# vca_B.net
KiCad netlist of a schematic drawn in Altium Designer
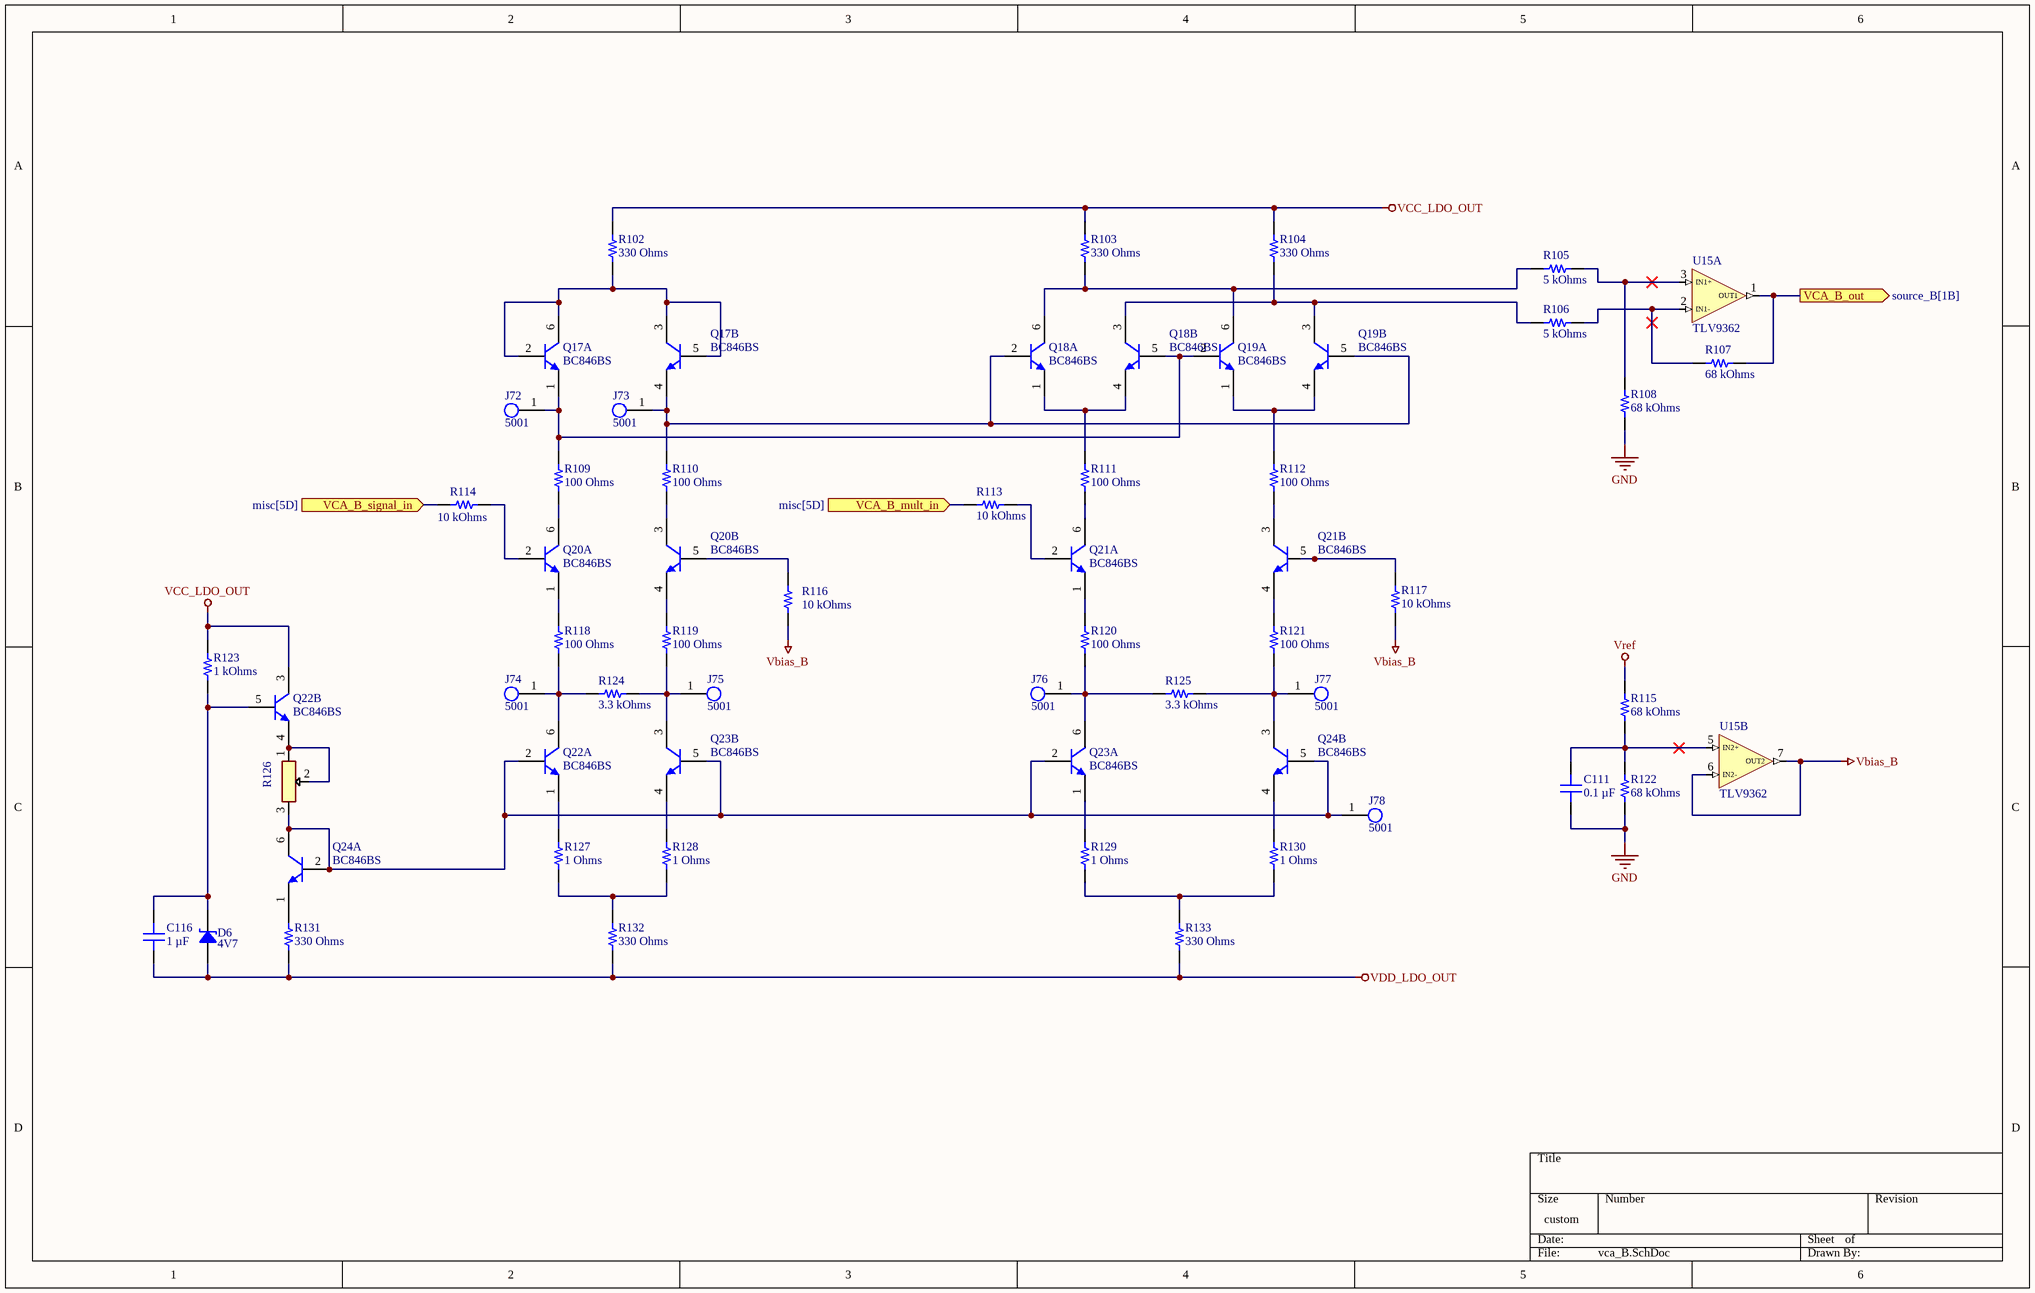
[diagram p0: vca_B.SchDoc]

(export (version "E")
  (design (tool "Eeschema 10.0.6"))
  (components
    (comp (ref "C111")
      (value "0.1 µF")
      (footprint "CAP 1206_3216 - 0.8MM")
      (description "CAP CER 0.1UF 50V X7R 1206")
      (fields
        (field (name "PART NUMBER") "885012208087")
        (field (name "CAPACITANCE") "0.1 µF")
        (field (name "MANUFACTURER") "Würth Elektronik")
      )
      (libsource (lib "Celestial Altium Library - altium_library") (part "Capacitor"))
    )
    (comp (ref "C116")
      (value "1 µF")
      (footprint "CAP 1206_3216 - 0.8MM")
      (description "CAP CER 1UF 50V X7R 1206")
      (fields
        (field (name "PART NUMBER") "885012208093")
        (field (name "CAPACITANCE") "1 µF")
        (field (name "MANUFACTURER") "Würth Elektronik")
      )
      (libsource (lib "Celestial Altium Library - altium_library") (part "Capacitor"))
    )
    (comp (ref "D6") (value "4V7") (footprint "SOD323") (libsource (lib "za_koncar") (part "BZX38450-C4V7X")))
    (comp (ref "J72")
      (value "5001")
      (footprint "FP-5001-MFG")
      (description "PC TEST POINT MINIATURE BLACK")
      (libsource (lib "za_koncar") (part "CMP-2000-05181-2"))
    )
    (comp (ref "J73")
      (value "5001")
      (footprint "FP-5001-MFG")
      (description "PC TEST POINT MINIATURE BLACK")
      (libsource (lib "za_koncar") (part "CMP-2000-05181-2"))
    )
    (comp (ref "J74")
      (value "5001")
      (footprint "FP-5001-MFG")
      (description "PC TEST POINT MINIATURE BLACK")
      (libsource (lib "za_koncar") (part "CMP-2000-05181-2"))
    )
    (comp (ref "J75")
      (value "5001")
      (footprint "FP-5001-MFG")
      (description "PC TEST POINT MINIATURE BLACK")
      (libsource (lib "za_koncar") (part "CMP-2000-05181-2"))
    )
    (comp (ref "J76")
      (value "5001")
      (footprint "FP-5001-MFG")
      (description "PC TEST POINT MINIATURE BLACK")
      (libsource (lib "za_koncar") (part "CMP-2000-05181-2"))
    )
    (comp (ref "J77")
      (value "5001")
      (footprint "FP-5001-MFG")
      (description "PC TEST POINT MINIATURE BLACK")
      (libsource (lib "za_koncar") (part "CMP-2000-05181-2"))
    )
    (comp (ref "J78")
      (value "5001")
      (footprint "FP-5001-MFG")
      (description "PC TEST POINT MINIATURE BLACK")
      (libsource (lib "za_koncar") (part "CMP-2000-05181-2"))
    )
    (comp (ref "Q17")
      (value "BC846BS")
      (footprint "TSOP65P210X110-6N")
      (description "65 V, 100 mA matched NPN/NPN general-purpose transistor")
      (libsource (lib "za_koncar") (part "BC846BS"))
    )
    (comp (ref "Q18")
      (value "BC846BS")
      (footprint "TSOP65P210X110-6N")
      (description "65 V, 100 mA matched NPN/NPN general-purpose transistor")
      (libsource (lib "za_koncar") (part "BC846BS"))
    )
    (comp (ref "Q19")
      (value "BC846BS")
      (footprint "TSOP65P210X110-6N")
      (description "65 V, 100 mA matched NPN/NPN general-purpose transistor")
      (libsource (lib "za_koncar") (part "BC846BS"))
    )
    (comp (ref "Q20")
      (value "BC846BS")
      (footprint "TSOP65P210X110-6N")
      (description "65 V, 100 mA matched NPN/NPN general-purpose transistor")
      (libsource (lib "za_koncar") (part "BC846BS"))
    )
    (comp (ref "Q21")
      (value "BC846BS")
      (footprint "TSOP65P210X110-6N")
      (description "65 V, 100 mA matched NPN/NPN general-purpose transistor")
      (libsource (lib "za_koncar") (part "BC846BS"))
    )
    (comp (ref "Q22")
      (value "BC846BS")
      (footprint "TSOP65P210X110-6N")
      (description "65 V, 100 mA matched NPN/NPN general-purpose transistor")
      (libsource (lib "za_koncar") (part "BC846BS"))
    )
    (comp (ref "Q23")
      (value "BC846BS")
      (footprint "TSOP65P210X110-6N")
      (description "65 V, 100 mA matched NPN/NPN general-purpose transistor")
      (libsource (lib "za_koncar") (part "BC846BS"))
    )
    (comp (ref "Q24")
      (value "BC846BS")
      (footprint "TSOP65P210X110-6N")
      (description "65 V, 100 mA matched NPN/NPN general-purpose transistor")
      (libsource (lib "za_koncar") (part "BC846BS"))
    )
    (comp (ref "R102")
      (value "330 Ohms")
      (footprint "YAGEO RES 1206_3216")
      (description "RES SMD 330 OHM 1% 1/4W 1206")
      (fields (field (name "PART NUMBER") "RT1206FRD07330RL") (field (name "MANUFACTURER") "Yageo"))
      (libsource (lib "Celestial Altium Library - altium_library") (part "Resistor"))
    )
    (comp (ref "R103")
      (value "330 Ohms")
      (footprint "YAGEO RES 1206_3216")
      (description "RES SMD 330 OHM 1% 1/4W 1206")
      (fields (field (name "PART NUMBER") "RT1206FRD07330RL") (field (name "MANUFACTURER") "Yageo"))
      (libsource (lib "Celestial Altium Library - altium_library") (part "Resistor"))
    )
    (comp (ref "R104")
      (value "330 Ohms")
      (footprint "YAGEO RES 1206_3216")
      (description "RES SMD 330 OHM 1% 1/4W 1206")
      (fields (field (name "PART NUMBER") "RT1206FRD07330RL") (field (name "MANUFACTURER") "Yageo"))
      (libsource (lib "Celestial Altium Library - altium_library") (part "Resistor"))
    )
    (comp (ref "R105")
      (value "5 kOhms")
      (footprint "YAGEO RES 1206_3216")
      (description "RES 5K OHM 1% 1/4W 1206")
      (fields (field (name "PART NUMBER") "RT1206FRE075KL") (field (name "MANUFACTURER") "Yageo"))
      (libsource (lib "Celestial Altium Library - altium_library") (part "Resistor"))
    )
    (comp (ref "R106")
      (value "5 kOhms")
      (footprint "YAGEO RES 1206_3216")
      (description "RES 5K OHM 1% 1/4W 1206")
      (fields (field (name "PART NUMBER") "RT1206FRE075KL") (field (name "MANUFACTURER") "Yageo"))
      (libsource (lib "Celestial Altium Library - altium_library") (part "Resistor"))
    )
    (comp (ref "R107")
      (value "68 kOhms")
      (footprint "YAGEO RES 1206_3216")
      (description "RES SMD 68K OHM 1% 1/4W 1206")
      (fields (field (name "PART NUMBER") "RT1206FRE0768KL") (field (name "MANUFACTURER") "Yageo"))
      (libsource (lib "Celestial Altium Library - altium_library") (part "Resistor"))
    )
    (comp (ref "R108")
      (value "68 kOhms")
      (footprint "YAGEO RES 1206_3216")
      (description "RES SMD 68K OHM 1% 1/4W 1206")
      (fields (field (name "PART NUMBER") "RT1206FRE0768KL") (field (name "MANUFACTURER") "Yageo"))
      (libsource (lib "Celestial Altium Library - altium_library") (part "Resistor"))
    )
    (comp (ref "R109")
      (value "100 Ohms")
      (footprint "YAGEO RES 1206_3216")
      (description "RES SMD 100 OHM 1% 1/4W 1206")
      (fields (field (name "PART NUMBER") "RT1206FRD07100RL") (field (name "MANUFACTURER") "Yageo"))
      (libsource (lib "Celestial Altium Library - altium_library") (part "Resistor"))
    )
    (comp (ref "R110")
      (value "100 Ohms")
      (footprint "YAGEO RES 1206_3216")
      (description "RES SMD 100 OHM 1% 1/4W 1206")
      (fields (field (name "PART NUMBER") "RT1206FRD07100RL") (field (name "MANUFACTURER") "Yageo"))
      (libsource (lib "Celestial Altium Library - altium_library") (part "Resistor"))
    )
    (comp (ref "R111")
      (value "100 Ohms")
      (footprint "YAGEO RES 1206_3216")
      (description "RES SMD 100 OHM 1% 1/4W 1206")
      (fields (field (name "PART NUMBER") "RT1206FRD07100RL") (field (name "MANUFACTURER") "Yageo"))
      (libsource (lib "Celestial Altium Library - altium_library") (part "Resistor"))
    )
    (comp (ref "R112")
      (value "100 Ohms")
      (footprint "YAGEO RES 1206_3216")
      (description "RES SMD 100 OHM 1% 1/4W 1206")
      (fields (field (name "PART NUMBER") "RT1206FRD07100RL") (field (name "MANUFACTURER") "Yageo"))
      (libsource (lib "Celestial Altium Library - altium_library") (part "Resistor"))
    )
    (comp (ref "R113")
      (value "10 kOhms")
      (footprint "YAGEO RES 1206_3216")
      (description "RES SMD 10K OHM 1% 1/4W 1206")
      (fields (field (name "PART NUMBER") "RT1206FRE0710KL") (field (name "MANUFACTURER") "Yageo"))
      (libsource (lib "Celestial Altium Library - altium_library") (part "Resistor"))
    )
    (comp (ref "R114")
      (value "10 kOhms")
      (footprint "YAGEO RES 1206_3216")
      (description "RES SMD 10K OHM 1% 1/4W 1206")
      (fields (field (name "PART NUMBER") "RT1206FRE0710KL") (field (name "MANUFACTURER") "Yageo"))
      (libsource (lib "Celestial Altium Library - altium_library") (part "Resistor"))
    )
    (comp (ref "R115")
      (value "68 kOhms")
      (footprint "YAGEO RES 1206_3216")
      (description "RES SMD 68K OHM 1% 1/4W 1206")
      (fields (field (name "PART NUMBER") "RT1206FRE0768KL") (field (name "MANUFACTURER") "Yageo"))
      (libsource (lib "Celestial Altium Library - altium_library") (part "Resistor"))
    )
    (comp (ref "R116")
      (value "10 kOhms")
      (footprint "YAGEO RES 1206_3216")
      (description "RES SMD 10K OHM 1% 1/4W 1206")
      (fields (field (name "PART NUMBER") "RT1206FRE0710KL") (field (name "MANUFACTURER") "Yageo"))
      (libsource (lib "Celestial Altium Library - altium_library") (part "Resistor"))
    )
    (comp (ref "R117")
      (value "10 kOhms")
      (footprint "YAGEO RES 1206_3216")
      (description "RES SMD 10K OHM 1% 1/4W 1206")
      (fields (field (name "PART NUMBER") "RT1206FRE0710KL") (field (name "MANUFACTURER") "Yageo"))
      (libsource (lib "Celestial Altium Library - altium_library") (part "Resistor"))
    )
    (comp (ref "R118")
      (value "100 Ohms")
      (footprint "YAGEO RES 1206_3216")
      (description "RES SMD 100 OHM 1% 1/4W 1206")
      (fields (field (name "PART NUMBER") "RT1206FRD07100RL") (field (name "MANUFACTURER") "Yageo"))
      (libsource (lib "Celestial Altium Library - altium_library") (part "Resistor"))
    )
    (comp (ref "R119")
      (value "100 Ohms")
      (footprint "YAGEO RES 1206_3216")
      (description "RES SMD 100 OHM 1% 1/4W 1206")
      (fields (field (name "PART NUMBER") "RT1206FRD07100RL") (field (name "MANUFACTURER") "Yageo"))
      (libsource (lib "Celestial Altium Library - altium_library") (part "Resistor"))
    )
    (comp (ref "R120")
      (value "100 Ohms")
      (footprint "YAGEO RES 1206_3216")
      (description "RES SMD 100 OHM 1% 1/4W 1206")
      (fields (field (name "PART NUMBER") "RT1206FRD07100RL") (field (name "MANUFACTURER") "Yageo"))
      (libsource (lib "Celestial Altium Library - altium_library") (part "Resistor"))
    )
    (comp (ref "R121")
      (value "100 Ohms")
      (footprint "YAGEO RES 1206_3216")
      (description "RES SMD 100 OHM 1% 1/4W 1206")
      (fields (field (name "PART NUMBER") "RT1206FRD07100RL") (field (name "MANUFACTURER") "Yageo"))
      (libsource (lib "Celestial Altium Library - altium_library") (part "Resistor"))
    )
    (comp (ref "R122")
      (value "68 kOhms")
      (footprint "YAGEO RES 1206_3216")
      (description "RES SMD 68K OHM 1% 1/4W 1206")
      (fields (field (name "PART NUMBER") "RT1206FRE0768KL") (field (name "MANUFACTURER") "Yageo"))
      (libsource (lib "Celestial Altium Library - altium_library") (part "Resistor"))
    )
    (comp (ref "R123")
      (value "1 kOhms")
      (footprint "YAGEO RES 1206_3216")
      (description "RES SMD 1K OHM 1% 1/4W 1206")
      (fields (field (name "PART NUMBER") "RT1206FRE071KL") (field (name "MANUFACTURER") "Yageo"))
      (libsource (lib "Celestial Altium Library - altium_library") (part "Resistor"))
    )
    (comp (ref "R124")
      (value "3.3 kOhms")
      (footprint "YAGEO RES 1206_3216")
      (description "RES SMD 3.3K OHM 1% 1/4W 1206")
      (fields (field (name "PART NUMBER") "RT1206FRE073K3L") (field (name "MANUFACTURER") "Yageo"))
      (libsource (lib "Celestial Altium Library - altium_library") (part "Resistor"))
    )
    (comp (ref "R125")
      (value "3.3 kOhms")
      (footprint "YAGEO RES 1206_3216")
      (description "RES SMD 3.3K OHM 1% 1/4W 1206")
      (fields (field (name "PART NUMBER") "RT1206FRE073K3L") (field (name "MANUFACTURER") "Yageo"))
      (libsource (lib "Celestial Altium Library - altium_library") (part "Resistor"))
    )
    (comp (ref "R126")
      (value "TC33X-2-502G")
      (footprint "TC33X2503E")
      (description "Resistor")
      (fields (field (name "MOUSER PART NUMBER") "652-TC33X-2-502G"))
      (libsource (lib "za_koncar") (part "TC33X-2-502G"))
    )
    (comp (ref "R127")
      (value "1 Ohms")
      (footprint "YAGEO RES 1206_3216")
      (description "RES 1 OHM 0.1% 1/4W 1206")
      (fields (field (name "PART NUMBER") "RT1206BRD071RL") (field (name "MANUFACTURER") "Yageo"))
      (libsource (lib "Celestial Altium Library - altium_library") (part "Resistor"))
    )
    (comp (ref "R128")
      (value "1 Ohms")
      (footprint "YAGEO RES 1206_3216")
      (description "RES 1 OHM 0.1% 1/4W 1206")
      (fields (field (name "PART NUMBER") "RT1206BRD071RL") (field (name "MANUFACTURER") "Yageo"))
      (libsource (lib "Celestial Altium Library - altium_library") (part "Resistor"))
    )
    (comp (ref "R129")
      (value "1 Ohms")
      (footprint "YAGEO RES 1206_3216")
      (description "RES 1 OHM 0.1% 1/4W 1206")
      (fields (field (name "PART NUMBER") "RT1206BRD071RL") (field (name "MANUFACTURER") "Yageo"))
      (libsource (lib "Celestial Altium Library - altium_library") (part "Resistor"))
    )
    (comp (ref "R130")
      (value "1 Ohms")
      (footprint "YAGEO RES 1206_3216")
      (description "RES 1 OHM 0.1% 1/4W 1206")
      (fields (field (name "PART NUMBER") "RT1206BRD071RL") (field (name "MANUFACTURER") "Yageo"))
      (libsource (lib "Celestial Altium Library - altium_library") (part "Resistor"))
    )
    (comp (ref "R131")
      (value "330 Ohms")
      (footprint "YAGEO RES 1206_3216")
      (description "RES SMD 330 OHM 1% 1/4W 1206")
      (fields (field (name "PART NUMBER") "RT1206FRD07330RL") (field (name "MANUFACTURER") "Yageo"))
      (libsource (lib "Celestial Altium Library - altium_library") (part "Resistor"))
    )
    (comp (ref "R132")
      (value "330 Ohms")
      (footprint "YAGEO RES 1206_3216")
      (description "RES SMD 330 OHM 1% 1/4W 1206")
      (fields (field (name "PART NUMBER") "RT1206FRD07330RL") (field (name "MANUFACTURER") "Yageo"))
      (libsource (lib "Celestial Altium Library - altium_library") (part "Resistor"))
    )
    (comp (ref "R133")
      (value "330 Ohms")
      (footprint "YAGEO RES 1206_3216")
      (description "RES SMD 330 OHM 1% 1/4W 1206")
      (fields (field (name "PART NUMBER") "RT1206FRD07330RL") (field (name "MANUFACTURER") "Yageo"))
      (libsource (lib "Celestial Altium Library - altium_library") (part "Resistor"))
    )
    (comp (ref "U15")
      (value "TLV9362")
      (footprint "za_koncar:SOIC8-127P600X175-8N")
      (description "TLV936x 10-MHz, 40-V, RRO, Operational Amplifie")
      (libsource (lib "za_koncar") (part "TLV9362"))
    )
  )
  (nets
    (net (code "1") (name "/VCA_B_mult_in") (class "Default")
      (node (ref "R113") (pin "1") (pinfunction "1_1") (pintype "passive"))
    )
    (net (code "2") (name "/VCA_B_out") (class "Default")
      (node (ref "R107") (pin "1") (pinfunction "1_1") (pintype "passive"))
      (node (ref "U15") (pin "1") (pinfunction "OUT1_1") (pintype "output"))
    )
    (net (code "3") (name "/VCA_B_signal_in") (class "Default")
      (node (ref "R114") (pin "1") (pinfunction "1_1") (pintype "passive"))
    )
    (net (code "4") (name "GND") (class "Default")
      (node (ref "C111") (pin "1") (pinfunction "1_1") (pintype "passive"))
      (node (ref "R108") (pin "2") (pinfunction "2_2") (pintype "passive"))
      (node (ref "R122") (pin "1") (pinfunction "1_1") (pintype "passive"))
    )
    (net (code "5") (name "Net-(Q17A-B1)") (class "Default")
      (node (ref "Q17") (pin "2") (pinfunction "B1_2") (pintype "passive"))
      (node (ref "Q17") (pin "3") (pinfunction "C2_3") (pintype "passive"))
      (node (ref "Q17") (pin "5") (pinfunction "B2_5") (pintype "passive"))
      (node (ref "Q17") (pin "6") (pinfunction "C1_6") (pintype "passive"))
      (node (ref "R102") (pin "1") (pinfunction "1_1") (pintype "passive"))
    )
    (net (code "6") (name "Net-(Q17A-E1)") (class "Default")
      (node (ref "J72") (pin "1") (pinfunction "1_1") (pintype "passive"))
      (node (ref "Q17") (pin "1") (pinfunction "E1_1") (pintype "passive"))
      (node (ref "Q18") (pin "5") (pinfunction "B2_5") (pintype "passive"))
      (node (ref "Q19") (pin "2") (pinfunction "B1_2") (pintype "passive"))
      (node (ref "R109") (pin "2") (pinfunction "2_2") (pintype "passive"))
    )
    (net (code "7") (name "Net-(Q17B-E2)") (class "Default")
      (node (ref "J73") (pin "1") (pinfunction "1_1") (pintype "passive"))
      (node (ref "Q17") (pin "4") (pinfunction "E2_4") (pintype "passive"))
      (node (ref "Q18") (pin "2") (pinfunction "B1_2") (pintype "passive"))
      (node (ref "Q19") (pin "5") (pinfunction "B2_5") (pintype "passive"))
      (node (ref "R110") (pin "2") (pinfunction "2_2") (pintype "passive"))
    )
    (net (code "8") (name "Net-(Q18A-C1)") (class "Default")
      (node (ref "Q18") (pin "6") (pinfunction "C1_6") (pintype "passive"))
      (node (ref "Q19") (pin "6") (pinfunction "C1_6") (pintype "passive"))
      (node (ref "R103") (pin "1") (pinfunction "1_1") (pintype "passive"))
      (node (ref "R105") (pin "2") (pinfunction "2_2") (pintype "passive"))
    )
    (net (code "9") (name "Net-(Q18A-E1)") (class "Default")
      (node (ref "Q18") (pin "1") (pinfunction "E1_1") (pintype "passive"))
      (node (ref "Q18") (pin "4") (pinfunction "E2_4") (pintype "passive"))
      (node (ref "R111") (pin "2") (pinfunction "2_2") (pintype "passive"))
    )
    (net (code "10") (name "Net-(Q18B-C2)") (class "Default")
      (node (ref "Q18") (pin "3") (pinfunction "C2_3") (pintype "passive"))
      (node (ref "Q19") (pin "3") (pinfunction "C2_3") (pintype "passive"))
      (node (ref "R104") (pin "1") (pinfunction "1_1") (pintype "passive"))
      (node (ref "R106") (pin "2") (pinfunction "2_2") (pintype "passive"))
    )
    (net (code "11") (name "Net-(Q19A-E1)") (class "Default")
      (node (ref "Q19") (pin "1") (pinfunction "E1_1") (pintype "passive"))
      (node (ref "Q19") (pin "4") (pinfunction "E2_4") (pintype "passive"))
      (node (ref "R112") (pin "2") (pinfunction "2_2") (pintype "passive"))
    )
    (net (code "12") (name "Net-(Q20A-B1)") (class "Default")
      (node (ref "Q20") (pin "2") (pinfunction "B1_2") (pintype "passive"))
      (node (ref "R114") (pin "2") (pinfunction "2_2") (pintype "passive"))
    )
    (net (code "13") (name "Net-(Q20A-C1)") (class "Default")
      (node (ref "Q20") (pin "6") (pinfunction "C1_6") (pintype "passive"))
      (node (ref "R109") (pin "1") (pinfunction "1_1") (pintype "passive"))
    )
    (net (code "14") (name "Net-(Q20A-E1)") (class "Default")
      (node (ref "Q20") (pin "1") (pinfunction "E1_1") (pintype "passive"))
      (node (ref "R118") (pin "2") (pinfunction "2_2") (pintype "passive"))
    )
    (net (code "15") (name "Net-(Q20B-B2)") (class "Default")
      (node (ref "Q20") (pin "5") (pinfunction "B2_5") (pintype "passive"))
      (node (ref "R116") (pin "2") (pinfunction "2_2") (pintype "passive"))
    )
    (net (code "16") (name "Net-(Q20B-C2)") (class "Default")
      (node (ref "Q20") (pin "3") (pinfunction "C2_3") (pintype "passive"))
      (node (ref "R110") (pin "1") (pinfunction "1_1") (pintype "passive"))
    )
    (net (code "17") (name "Net-(Q20B-E2)") (class "Default")
      (node (ref "Q20") (pin "4") (pinfunction "E2_4") (pintype "passive"))
      (node (ref "R119") (pin "2") (pinfunction "2_2") (pintype "passive"))
    )
    (net (code "18") (name "Net-(Q21A-B1)") (class "Default")
      (node (ref "Q21") (pin "2") (pinfunction "B1_2") (pintype "passive"))
      (node (ref "R113") (pin "2") (pinfunction "2_2") (pintype "passive"))
    )
    (net (code "19") (name "Net-(Q21A-C1)") (class "Default")
      (node (ref "Q21") (pin "6") (pinfunction "C1_6") (pintype "passive"))
      (node (ref "R111") (pin "1") (pinfunction "1_1") (pintype "passive"))
    )
    (net (code "20") (name "Net-(Q21A-E1)") (class "Default")
      (node (ref "Q21") (pin "1") (pinfunction "E1_1") (pintype "passive"))
      (node (ref "R120") (pin "2") (pinfunction "2_2") (pintype "passive"))
    )
    (net (code "21") (name "Net-(Q21B-B2)") (class "Default")
      (node (ref "Q21") (pin "5") (pinfunction "B2_5") (pintype "passive"))
      (node (ref "R117") (pin "2") (pinfunction "2_2") (pintype "passive"))
    )
    (net (code "22") (name "Net-(Q21B-C2)") (class "Default")
      (node (ref "Q21") (pin "3") (pinfunction "C2_3") (pintype "passive"))
      (node (ref "R112") (pin "1") (pinfunction "1_1") (pintype "passive"))
    )
    (net (code "23") (name "Net-(Q21B-E2)") (class "Default")
      (node (ref "Q21") (pin "4") (pinfunction "E2_4") (pintype "passive"))
      (node (ref "R121") (pin "2") (pinfunction "2_2") (pintype "passive"))
    )
    (net (code "24") (name "Net-(Q22A-B1)") (class "Default")
      (node (ref "J78") (pin "1") (pinfunction "1_1") (pintype "passive"))
      (node (ref "Q22") (pin "2") (pinfunction "B1_2") (pintype "passive"))
      (node (ref "Q23") (pin "2") (pinfunction "B1_2") (pintype "passive"))
      (node (ref "Q23") (pin "5") (pinfunction "B2_5") (pintype "passive"))
      (node (ref "Q24") (pin "2") (pinfunction "B1_2") (pintype "passive"))
      (node (ref "Q24") (pin "5") (pinfunction "B2_5") (pintype "passive"))
      (node (ref "Q24") (pin "6") (pinfunction "C1_6") (pintype "passive"))
      (node (ref "R126") (pin "3") (pinfunction "CW_3") (pintype "passive"))
    )
    (net (code "25") (name "Net-(Q22A-C1)") (class "Default")
      (node (ref "J74") (pin "1") (pinfunction "1_1") (pintype "passive"))
      (node (ref "Q22") (pin "6") (pinfunction "C1_6") (pintype "passive"))
      (node (ref "R118") (pin "1") (pinfunction "1_1") (pintype "passive"))
      (node (ref "R124") (pin "2") (pinfunction "2_2") (pintype "passive"))
    )
    (net (code "26") (name "Net-(Q22A-E1)") (class "Default")
      (node (ref "Q22") (pin "1") (pinfunction "E1_1") (pintype "passive"))
      (node (ref "R127") (pin "2") (pinfunction "2_2") (pintype "passive"))
    )
    (net (code "27") (name "Net-(Q22B-B2)") (class "Default")
      (node (ref "C116") (pin "2") (pinfunction "2_2") (pintype "passive"))
      (node (ref "D6") (pin "2") (pinfunction "2_2") (pintype "passive"))
      (node (ref "Q22") (pin "5") (pinfunction "B2_5") (pintype "passive"))
      (node (ref "R123") (pin "1") (pinfunction "1_1") (pintype "passive"))
    )
    (net (code "28") (name "Net-(Q22B-E2)") (class "Default")
      (node (ref "Q22") (pin "4") (pinfunction "E2_4") (pintype "passive"))
      (node (ref "R126") (pin "1") (pinfunction "CCW_1") (pintype "passive"))
      (node (ref "R126") (pin "2") (pinfunction "W_2") (pintype "passive"))
    )
    (net (code "29") (name "Net-(Q23A-C1)") (class "Default")
      (node (ref "J76") (pin "1") (pinfunction "1_1") (pintype "passive"))
      (node (ref "Q23") (pin "6") (pinfunction "C1_6") (pintype "passive"))
      (node (ref "R120") (pin "1") (pinfunction "1_1") (pintype "passive"))
      (node (ref "R125") (pin "2") (pinfunction "2_2") (pintype "passive"))
    )
    (net (code "30") (name "Net-(Q23A-E1)") (class "Default")
      (node (ref "Q23") (pin "1") (pinfunction "E1_1") (pintype "passive"))
      (node (ref "R129") (pin "2") (pinfunction "2_2") (pintype "passive"))
    )
    (net (code "31") (name "Net-(Q23B-C2)") (class "Default")
      (node (ref "J75") (pin "1") (pinfunction "1_1") (pintype "passive"))
      (node (ref "Q23") (pin "3") (pinfunction "C2_3") (pintype "passive"))
      (node (ref "R119") (pin "1") (pinfunction "1_1") (pintype "passive"))
      (node (ref "R124") (pin "1") (pinfunction "1_1") (pintype "passive"))
    )
    (net (code "32") (name "Net-(Q23B-E2)") (class "Default")
      (node (ref "Q23") (pin "4") (pinfunction "E2_4") (pintype "passive"))
      (node (ref "R128") (pin "2") (pinfunction "2_2") (pintype "passive"))
    )
    (net (code "33") (name "Net-(Q24A-E1)") (class "Default")
      (node (ref "Q24") (pin "1") (pinfunction "E1_1") (pintype "passive"))
      (node (ref "R131") (pin "2") (pinfunction "2_2") (pintype "passive"))
    )
    (net (code "34") (name "Net-(Q24B-C2)") (class "Default")
      (node (ref "J77") (pin "1") (pinfunction "1_1") (pintype "passive"))
      (node (ref "Q24") (pin "3") (pinfunction "C2_3") (pintype "passive"))
      (node (ref "R121") (pin "1") (pinfunction "1_1") (pintype "passive"))
      (node (ref "R125") (pin "1") (pinfunction "1_1") (pintype "passive"))
    )
    (net (code "35") (name "Net-(Q24B-E2)") (class "Default")
      (node (ref "Q24") (pin "4") (pinfunction "E2_4") (pintype "passive"))
      (node (ref "R130") (pin "2") (pinfunction "2_2") (pintype "passive"))
    )
    (net (code "36") (name "Net-(R127-Pad1)") (class "Default")
      (node (ref "R127") (pin "1") (pinfunction "1_1") (pintype "passive"))
      (node (ref "R128") (pin "1") (pinfunction "1_1") (pintype "passive"))
      (node (ref "R132") (pin "2") (pinfunction "2_2") (pintype "passive"))
    )
    (net (code "37") (name "Net-(R129-Pad1)") (class "Default")
      (node (ref "R129") (pin "1") (pinfunction "1_1") (pintype "passive"))
      (node (ref "R130") (pin "1") (pinfunction "1_1") (pintype "passive"))
      (node (ref "R133") (pin "2") (pinfunction "2_2") (pintype "passive"))
    )
    (net (code "38") (name "Net-(U15A-IN1+)") (class "Default")
      (node (ref "R105") (pin "1") (pinfunction "1_1") (pintype "passive"))
      (node (ref "R108") (pin "1") (pinfunction "1_1") (pintype "passive"))
      (node (ref "U15") (pin "3") (pinfunction "IN1+_3") (pintype "input"))
    )
    (net (code "39") (name "Net-(U15A-IN1-)") (class "Default")
      (node (ref "R106") (pin "1") (pinfunction "1_1") (pintype "passive"))
      (node (ref "R107") (pin "2") (pinfunction "2_2") (pintype "passive"))
      (node (ref "U15") (pin "2") (pinfunction "IN1-_2") (pintype "input"))
    )
    (net (code "40") (name "Net-(U15B-IN2+)") (class "Default")
      (node (ref "C111") (pin "2") (pinfunction "2_2") (pintype "passive"))
      (node (ref "R115") (pin "1") (pinfunction "1_1") (pintype "passive"))
      (node (ref "R122") (pin "2") (pinfunction "2_2") (pintype "passive"))
      (node (ref "U15") (pin "5") (pinfunction "IN2+_5") (pintype "input"))
    )
    (net (code "41") (name "VCC_LDO_OUT") (class "Default")
      (node (ref "Q22") (pin "3") (pinfunction "C2_3") (pintype "passive"))
      (node (ref "R102") (pin "2") (pinfunction "2_2") (pintype "passive"))
      (node (ref "R103") (pin "2") (pinfunction "2_2") (pintype "passive"))
      (node (ref "R104") (pin "2") (pinfunction "2_2") (pintype "passive"))
      (node (ref "R123") (pin "2") (pinfunction "2_2") (pintype "passive"))
    )
    (net (code "42") (name "VDD_LDO_OUT") (class "Default")
      (node (ref "C116") (pin "1") (pinfunction "1_1") (pintype "passive"))
      (node (ref "D6") (pin "1") (pinfunction "1_1") (pintype "passive"))
      (node (ref "R131") (pin "1") (pinfunction "1_1") (pintype "passive"))
      (node (ref "R132") (pin "1") (pinfunction "1_1") (pintype "passive"))
      (node (ref "R133") (pin "1") (pinfunction "1_1") (pintype "passive"))
    )
    (net (code "43") (name "Vbias_B") (class "Default")
      (node (ref "R116") (pin "1") (pinfunction "1_1") (pintype "passive"))
      (node (ref "R117") (pin "1") (pinfunction "1_1") (pintype "passive"))
      (node (ref "U15") (pin "6") (pinfunction "IN2-_6") (pintype "input"))
      (node (ref "U15") (pin "7") (pinfunction "OUT2_7") (pintype "output"))
    )
    (net (code "44") (name "Vref") (class "Default")
      (node (ref "R115") (pin "2") (pinfunction "2_2") (pintype "passive"))
    )
  )
)
